# BLUESAT_WIRING_HARNESS_-_PROPOSED_V2.net
KiCad netlist of a schematic drawn in Altium Designer
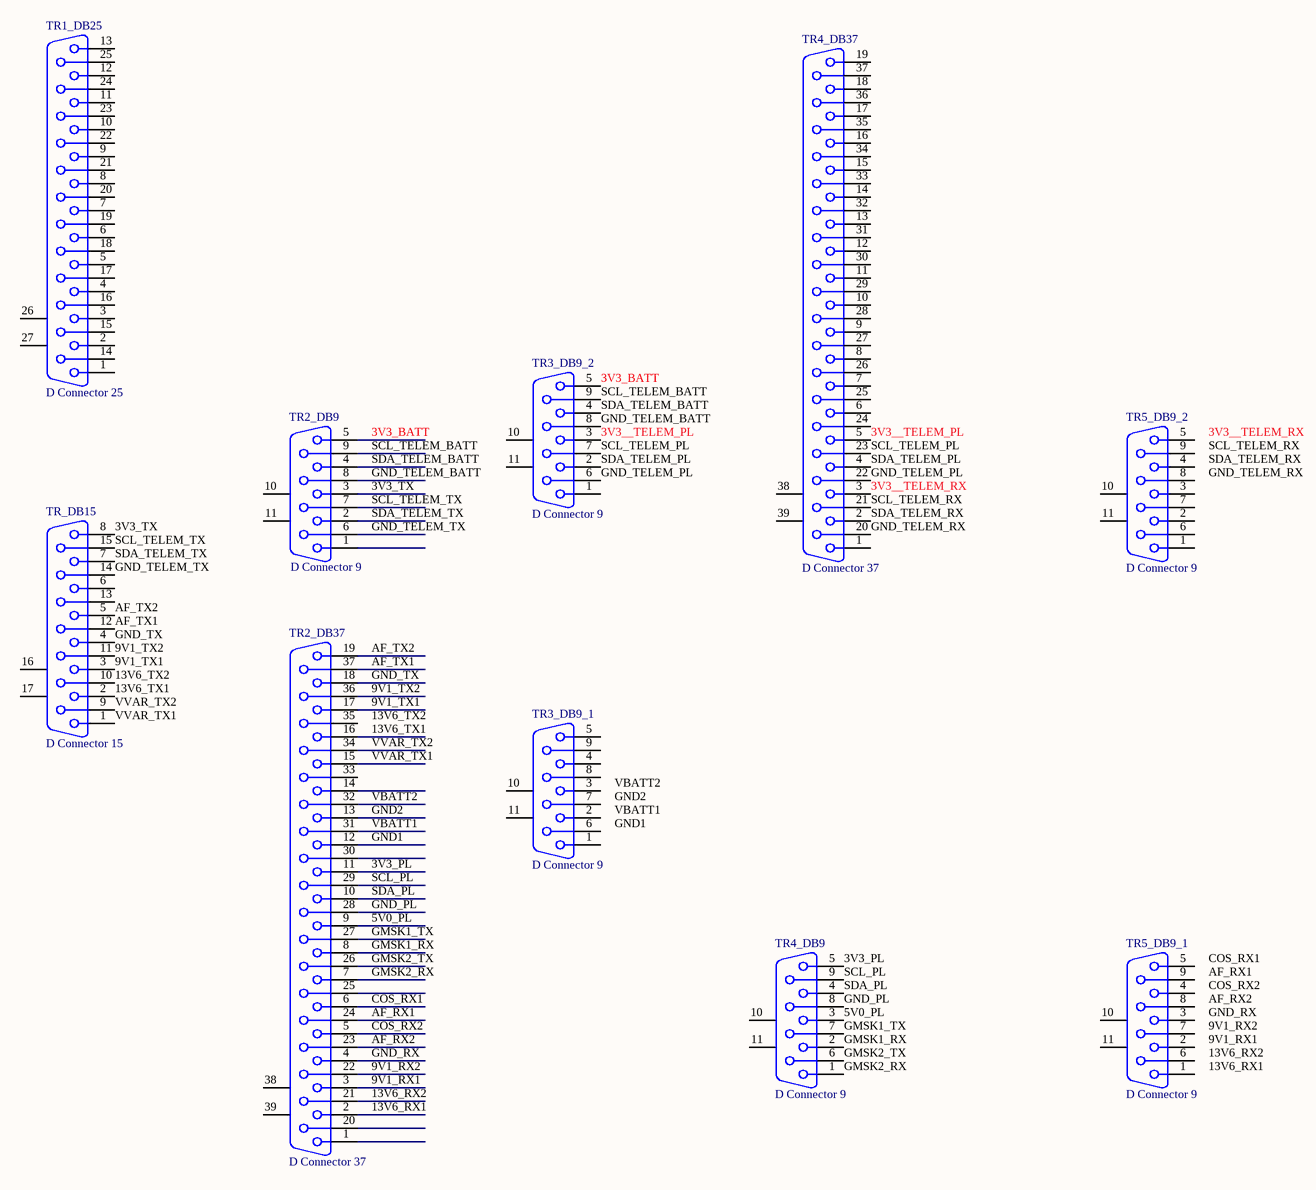
[diagram p0: BLUESAT WIRING HARNESS - PROPOSED V2.SchDoc]

(export (version "E")
  (design (tool "Eeschema 10.0.6"))
  (components
    (comp (ref "TR1_DB25")
      (value "D Connector 25")
      (footprint "DSUB1.385-2H25A")
      (description "Receptacle Assembly, 25 Position, Right Angle")
      (fields (field (name "PUBLISHER") "Altium Limited"))
      (libsource (lib "Miscellaneous Connectors") (part "D Connector 25"))
    )
    (comp (ref "TR2_DB9")
      (value "D Connector 9")
      (footprint "DSUB1.385-2H9")
      (description "Receptacle Assembly, 9 Position, Right Angle")
      (fields (field (name "PUBLISHER") "Altium Limited"))
      (libsource (lib "Miscellaneous Connectors") (part "D Connector 9"))
    )
    (comp (ref "TR2_DB37")
      (value "D Connector 37")
      (description "Receptacle Assembly, 37 Position, Right Angle")
      (fields (field (name "PUBLISHER") "Altium Limited"))
      (libsource (lib "Miscellaneous Connectors") (part "D Connector 37"))
    )
    (comp (ref "TR3_DB9_1")
      (value "D Connector 9")
      (footprint "DSUB1.385-2H9")
      (description "Receptacle Assembly, 9 Position, Right Angle")
      (fields (field (name "PUBLISHER") "Altium Limited"))
      (libsource (lib "Miscellaneous Connectors") (part "D Connector 9"))
    )
    (comp (ref "TR3_DB9_2")
      (value "D Connector 9")
      (footprint "DSUB1.385-2H9")
      (description "Receptacle Assembly, 9 Position, Right Angle")
      (fields (field (name "PUBLISHER") "Altium Limited"))
      (libsource (lib "Miscellaneous Connectors") (part "D Connector 9"))
    )
    (comp (ref "TR4_DB9")
      (value "D Connector 9")
      (footprint "DSUB1.385-2H9")
      (description "Receptacle Assembly, 9 Position, Right Angle")
      (fields (field (name "PUBLISHER") "Altium Limited"))
      (libsource (lib "Miscellaneous Connectors") (part "D Connector 9"))
    )
    (comp (ref "TR4_DB37")
      (value "D Connector 37")
      (description "Receptacle Assembly, 37 Position, Right Angle")
      (fields (field (name "PUBLISHER") "Altium Limited"))
      (libsource (lib "Miscellaneous Connectors") (part "D Connector 37"))
    )
    (comp (ref "TR5_DB9_1")
      (value "D Connector 9")
      (footprint "DSUB1.385-2H9")
      (description "Receptacle Assembly, 9 Position, Right Angle")
      (fields (field (name "PUBLISHER") "Altium Limited"))
      (libsource (lib "Miscellaneous Connectors") (part "D Connector 9"))
    )
    (comp (ref "TR5_DB9_2")
      (value "D Connector 9")
      (footprint "DSUB1.385-2H9")
      (description "Receptacle Assembly, 9 Position, Right Angle")
      (fields (field (name "PUBLISHER") "Altium Limited"))
      (libsource (lib "Miscellaneous Connectors") (part "D Connector 9"))
    )
    (comp (ref "TR_DB15")
      (value "D Connector 15")
      (footprint "DSUB1.385-2H15")
      (description "Receptacle Assembly, 15 Position, Right Angle")
      (fields (field (name "PUBLISHER") "Altium Limited"))
      (libsource (lib "Miscellaneous Connectors") (part "D Connector 15"))
    )
  )
  (nets
    (net (code "1") (name "/3V3_BATT") (class "Default")
      (node (ref "TR2_DB9") (pin "5") (pinfunction "5_5") (pintype "passive"))
      (node (ref "TR3_DB9_2") (pin "5") (pinfunction "5_5") (pintype "passive"))
    )
    (net (code "2") (name "/3V3_PL") (class "Default")
      (node (ref "TR2_DB37") (pin "11") (pinfunction "11_11") (pintype "passive"))
      (node (ref "TR4_DB9") (pin "5") (pinfunction "5_5") (pintype "passive"))
    )
    (net (code "3") (name "/3V3_TX") (class "Default")
      (node (ref "TR2_DB9") (pin "3") (pinfunction "3_3") (pintype "passive"))
      (node (ref "TR_DB15") (pin "8") (pinfunction "8_8") (pintype "passive"))
    )
    (net (code "4") (name "/3V3__TELEM_PL") (class "Default")
      (node (ref "TR3_DB9_2") (pin "3") (pinfunction "3_3") (pintype "passive"))
      (node (ref "TR4_DB37") (pin "5") (pinfunction "5_5") (pintype "passive"))
    )
    (net (code "5") (name "/3V3__TELEM_RX") (class "Default")
      (node (ref "TR4_DB37") (pin "3") (pinfunction "3_3") (pintype "passive"))
    )
    (net (code "6") (name "/5V0_PL") (class "Default")
      (node (ref "TR2_DB37") (pin "9") (pinfunction "9_9") (pintype "passive"))
      (node (ref "TR4_DB9") (pin "3") (pinfunction "3_3") (pintype "passive"))
    )
    (net (code "7") (name "/9V1_RX1") (class "Default")
      (node (ref "TR2_DB37") (pin "3") (pinfunction "3_3") (pintype "passive"))
    )
    (net (code "8") (name "/9V1_RX2") (class "Default")
      (node (ref "TR2_DB37") (pin "22") (pinfunction "22_22") (pintype "passive"))
    )
    (net (code "9") (name "/9V1_TX1") (class "Default")
      (node (ref "TR2_DB37") (pin "17") (pinfunction "17_17") (pintype "passive"))
      (node (ref "TR_DB15") (pin "3") (pinfunction "3_3") (pintype "passive"))
    )
    (net (code "10") (name "/9V1_TX2") (class "Default")
      (node (ref "TR2_DB37") (pin "36") (pinfunction "36_36") (pintype "passive"))
      (node (ref "TR_DB15") (pin "11") (pinfunction "11_11") (pintype "passive"))
    )
    (net (code "11") (name "/13V6_RX1") (class "Default")
      (node (ref "TR2_DB37") (pin "2") (pinfunction "2_2") (pintype "passive"))
    )
    (net (code "12") (name "/13V6_RX2") (class "Default")
      (node (ref "TR2_DB37") (pin "21") (pinfunction "21_21") (pintype "passive"))
    )
    (net (code "13") (name "/13V6_TX1") (class "Default")
      (node (ref "TR2_DB37") (pin "16") (pinfunction "16_16") (pintype "passive"))
      (node (ref "TR_DB15") (pin "2") (pinfunction "2_2") (pintype "passive"))
    )
    (net (code "14") (name "/13V6_TX2") (class "Default")
      (node (ref "TR_DB15") (pin "10") (pinfunction "10_10") (pintype "passive"))
    )
    (net (code "15") (name "/AF_RX1") (class "Default")
      (node (ref "TR2_DB37") (pin "24") (pinfunction "24_24") (pintype "passive"))
    )
    (net (code "16") (name "/AF_RX2") (class "Default")
      (node (ref "TR2_DB37") (pin "23") (pinfunction "23_23") (pintype "passive"))
    )
    (net (code "17") (name "/AF_TX1") (class "Default")
      (node (ref "TR2_DB37") (pin "37") (pinfunction "37_37") (pintype "passive"))
      (node (ref "TR_DB15") (pin "12") (pinfunction "12_12") (pintype "passive"))
    )
    (net (code "18") (name "/AF_TX2") (class "Default")
      (node (ref "TR2_DB37") (pin "19") (pinfunction "19_19") (pintype "passive"))
      (node (ref "TR_DB15") (pin "5") (pinfunction "5_5") (pintype "passive"))
    )
    (net (code "19") (name "/COS_RX1") (class "Default")
      (node (ref "TR2_DB37") (pin "6") (pinfunction "6_6") (pintype "passive"))
    )
    (net (code "20") (name "/COS_RX2") (class "Default")
      (node (ref "TR2_DB37") (pin "5") (pinfunction "5_5") (pintype "passive"))
    )
    (net (code "21") (name "/GMSK1_RX") (class "Default")
      (node (ref "TR2_DB37") (pin "8") (pinfunction "8_8") (pintype "passive"))
      (node (ref "TR4_DB9") (pin "2") (pinfunction "2_2") (pintype "passive"))
    )
    (net (code "22") (name "/GMSK1_TX") (class "Default")
      (node (ref "TR2_DB37") (pin "27") (pinfunction "27_27") (pintype "passive"))
      (node (ref "TR4_DB9") (pin "7") (pinfunction "7_7") (pintype "passive"))
    )
    (net (code "23") (name "/GMSK2_RX") (class "Default")
      (node (ref "TR2_DB37") (pin "7") (pinfunction "7_7") (pintype "passive"))
      (node (ref "TR4_DB9") (pin "1") (pinfunction "1_1") (pintype "passive"))
    )
    (net (code "24") (name "/GMSK2_TX") (class "Default")
      (node (ref "TR2_DB37") (pin "26") (pinfunction "26_26") (pintype "passive"))
      (node (ref "TR4_DB9") (pin "6") (pinfunction "6_6") (pintype "passive"))
    )
    (net (code "25") (name "/GND1") (class "Default")
      (node (ref "TR2_DB37") (pin "12") (pinfunction "12_12") (pintype "passive"))
    )
    (net (code "26") (name "/GND2") (class "Default")
      (node (ref "TR2_DB37") (pin "13") (pinfunction "13_13") (pintype "passive"))
    )
    (net (code "27") (name "/GND_PL") (class "Default")
      (node (ref "TR2_DB37") (pin "28") (pinfunction "28_28") (pintype "passive"))
      (node (ref "TR4_DB9") (pin "8") (pinfunction "8_8") (pintype "passive"))
    )
    (net (code "28") (name "/GND_RX") (class "Default")
      (node (ref "TR2_DB37") (pin "4") (pinfunction "4_4") (pintype "passive"))
    )
    (net (code "29") (name "/GND_TELEM_BATT") (class "Default")
      (node (ref "TR2_DB9") (pin "8") (pinfunction "8_8") (pintype "passive"))
      (node (ref "TR3_DB9_2") (pin "8") (pinfunction "8_8") (pintype "passive"))
    )
    (net (code "30") (name "/GND_TELEM_PL") (class "Default")
      (node (ref "TR3_DB9_2") (pin "6") (pinfunction "6_6") (pintype "passive"))
      (node (ref "TR4_DB37") (pin "22") (pinfunction "22_22") (pintype "passive"))
    )
    (net (code "31") (name "/GND_TELEM_RX") (class "Default")
      (node (ref "TR4_DB37") (pin "20") (pinfunction "20_20") (pintype "passive"))
    )
    (net (code "32") (name "/GND_TELEM_TX") (class "Default")
      (node (ref "TR2_DB9") (pin "6") (pinfunction "6_6") (pintype "passive"))
      (node (ref "TR_DB15") (pin "14") (pinfunction "14_14") (pintype "passive"))
    )
    (net (code "33") (name "/GND_TX") (class "Default")
      (node (ref "TR2_DB37") (pin "18") (pinfunction "18_18") (pintype "passive"))
      (node (ref "TR_DB15") (pin "4") (pinfunction "4_4") (pintype "passive"))
    )
    (net (code "34") (name "/SCL_PL") (class "Default")
      (node (ref "TR2_DB37") (pin "29") (pinfunction "29_29") (pintype "passive"))
      (node (ref "TR4_DB9") (pin "9") (pinfunction "9_9") (pintype "passive"))
    )
    (net (code "35") (name "/SCL_TELEM_BATT") (class "Default")
      (node (ref "TR2_DB9") (pin "9") (pinfunction "9_9") (pintype "passive"))
      (node (ref "TR3_DB9_2") (pin "9") (pinfunction "9_9") (pintype "passive"))
    )
    (net (code "36") (name "/SCL_TELEM_PL") (class "Default")
      (node (ref "TR3_DB9_2") (pin "7") (pinfunction "7_7") (pintype "passive"))
      (node (ref "TR4_DB37") (pin "23") (pinfunction "23_23") (pintype "passive"))
    )
    (net (code "37") (name "/SCL_TELEM_RX") (class "Default")
      (node (ref "TR4_DB37") (pin "21") (pinfunction "21_21") (pintype "passive"))
    )
    (net (code "38") (name "/SCL_TELEM_TX") (class "Default")
      (node (ref "TR2_DB9") (pin "7") (pinfunction "7_7") (pintype "passive"))
      (node (ref "TR_DB15") (pin "15") (pinfunction "15_15") (pintype "passive"))
    )
    (net (code "39") (name "/SDA_PL") (class "Default")
      (node (ref "TR2_DB37") (pin "10") (pinfunction "10_10") (pintype "passive"))
      (node (ref "TR4_DB9") (pin "4") (pinfunction "4_4") (pintype "passive"))
    )
    (net (code "40") (name "/SDA_TELEM_BATT") (class "Default")
      (node (ref "TR2_DB9") (pin "4") (pinfunction "4_4") (pintype "passive"))
      (node (ref "TR3_DB9_2") (pin "4") (pinfunction "4_4") (pintype "passive"))
    )
    (net (code "41") (name "/SDA_TELEM_PL") (class "Default")
      (node (ref "TR3_DB9_2") (pin "2") (pinfunction "2_2") (pintype "passive"))
      (node (ref "TR4_DB37") (pin "4") (pinfunction "4_4") (pintype "passive"))
    )
    (net (code "42") (name "/SDA_TELEM_RX") (class "Default")
      (node (ref "TR4_DB37") (pin "2") (pinfunction "2_2") (pintype "passive"))
    )
    (net (code "43") (name "/SDA_TELEM_TX") (class "Default")
      (node (ref "TR2_DB9") (pin "2") (pinfunction "2_2") (pintype "passive"))
      (node (ref "TR_DB15") (pin "7") (pinfunction "7_7") (pintype "passive"))
    )
    (net (code "44") (name "/VBATT1") (class "Default")
      (node (ref "TR2_DB37") (pin "31") (pinfunction "31_31") (pintype "passive"))
    )
    (net (code "45") (name "/VBATT2") (class "Default")
      (node (ref "TR2_DB37") (pin "32") (pinfunction "32_32") (pintype "passive"))
    )
    (net (code "46") (name "/VVAR_TX1") (class "Default")
      (node (ref "TR2_DB37") (pin "15") (pinfunction "15_15") (pintype "passive"))
      (node (ref "TR_DB15") (pin "1") (pinfunction "1_1") (pintype "passive"))
    )
    (net (code "47") (name "/VVAR_TX2") (class "Default")
      (node (ref "TR2_DB37") (pin "34") (pinfunction "34_34") (pintype "passive"))
      (node (ref "TR_DB15") (pin "9") (pinfunction "9_9") (pintype "passive"))
    )
    (net (code "48") (name "unconnected-(TR1_DB25-MH1-Pad26)") (class "Default")
      (node (ref "TR1_DB25") (pin "26") (pinfunction "MH1_26") (pintype "passive"))
    )
    (net (code "49") (name "unconnected-(TR1_DB25-MH2-Pad27)") (class "Default")
      (node (ref "TR1_DB25") (pin "27") (pinfunction "MH2_27") (pintype "passive"))
    )
    (net (code "50") (name "unconnected-(TR1_DB25-Pad1)") (class "Default")
      (node (ref "TR1_DB25") (pin "1") (pinfunction "1_1") (pintype "passive"))
    )
    (net (code "51") (name "unconnected-(TR1_DB25-Pad2)") (class "Default")
      (node (ref "TR1_DB25") (pin "2") (pinfunction "2_2") (pintype "passive"))
    )
    (net (code "52") (name "unconnected-(TR1_DB25-Pad3)") (class "Default")
      (node (ref "TR1_DB25") (pin "3") (pinfunction "3_3") (pintype "passive"))
    )
    (net (code "53") (name "unconnected-(TR1_DB25-Pad4)") (class "Default")
      (node (ref "TR1_DB25") (pin "4") (pinfunction "4_4") (pintype "passive"))
    )
    (net (code "54") (name "unconnected-(TR1_DB25-Pad5)") (class "Default")
      (node (ref "TR1_DB25") (pin "5") (pinfunction "5_5") (pintype "passive"))
    )
    (net (code "55") (name "unconnected-(TR1_DB25-Pad6)") (class "Default")
      (node (ref "TR1_DB25") (pin "6") (pinfunction "6_6") (pintype "passive"))
    )
    (net (code "56") (name "unconnected-(TR1_DB25-Pad7)") (class "Default")
      (node (ref "TR1_DB25") (pin "7") (pinfunction "7_7") (pintype "passive"))
    )
    (net (code "57") (name "unconnected-(TR1_DB25-Pad8)") (class "Default")
      (node (ref "TR1_DB25") (pin "8") (pinfunction "8_8") (pintype "passive"))
    )
    (net (code "58") (name "unconnected-(TR1_DB25-Pad9)") (class "Default")
      (node (ref "TR1_DB25") (pin "9") (pinfunction "9_9") (pintype "passive"))
    )
    (net (code "59") (name "unconnected-(TR1_DB25-Pad10)") (class "Default")
      (node (ref "TR1_DB25") (pin "10") (pinfunction "10_10") (pintype "passive"))
    )
    (net (code "60") (name "unconnected-(TR1_DB25-Pad11)") (class "Default")
      (node (ref "TR1_DB25") (pin "11") (pinfunction "11_11") (pintype "passive"))
    )
    (net (code "61") (name "unconnected-(TR1_DB25-Pad12)") (class "Default")
      (node (ref "TR1_DB25") (pin "12") (pinfunction "12_12") (pintype "passive"))
    )
    (net (code "62") (name "unconnected-(TR1_DB25-Pad13)") (class "Default")
      (node (ref "TR1_DB25") (pin "13") (pinfunction "13_13") (pintype "passive"))
    )
    (net (code "63") (name "unconnected-(TR1_DB25-Pad14)") (class "Default")
      (node (ref "TR1_DB25") (pin "14") (pinfunction "14_14") (pintype "passive"))
    )
    (net (code "64") (name "unconnected-(TR1_DB25-Pad15)") (class "Default")
      (node (ref "TR1_DB25") (pin "15") (pinfunction "15_15") (pintype "passive"))
    )
    (net (code "65") (name "unconnected-(TR1_DB25-Pad16)") (class "Default")
      (node (ref "TR1_DB25") (pin "16") (pinfunction "16_16") (pintype "passive"))
    )
    (net (code "66") (name "unconnected-(TR1_DB25-Pad17)") (class "Default")
      (node (ref "TR1_DB25") (pin "17") (pinfunction "17_17") (pintype "passive"))
    )
    (net (code "67") (name "unconnected-(TR1_DB25-Pad18)") (class "Default")
      (node (ref "TR1_DB25") (pin "18") (pinfunction "18_18") (pintype "passive"))
    )
    (net (code "68") (name "unconnected-(TR1_DB25-Pad19)") (class "Default")
      (node (ref "TR1_DB25") (pin "19") (pinfunction "19_19") (pintype "passive"))
    )
    (net (code "69") (name "unconnected-(TR1_DB25-Pad20)") (class "Default")
      (node (ref "TR1_DB25") (pin "20") (pinfunction "20_20") (pintype "passive"))
    )
    (net (code "70") (name "unconnected-(TR1_DB25-Pad21)") (class "Default")
      (node (ref "TR1_DB25") (pin "21") (pinfunction "21_21") (pintype "passive"))
    )
    (net (code "71") (name "unconnected-(TR1_DB25-Pad22)") (class "Default")
      (node (ref "TR1_DB25") (pin "22") (pinfunction "22_22") (pintype "passive"))
    )
    (net (code "72") (name "unconnected-(TR1_DB25-Pad23)") (class "Default")
      (node (ref "TR1_DB25") (pin "23") (pinfunction "23_23") (pintype "passive"))
    )
    (net (code "73") (name "unconnected-(TR1_DB25-Pad24)") (class "Default")
      (node (ref "TR1_DB25") (pin "24") (pinfunction "24_24") (pintype "passive"))
    )
    (net (code "74") (name "unconnected-(TR1_DB25-Pad25)") (class "Default")
      (node (ref "TR1_DB25") (pin "25") (pinfunction "25_25") (pintype "passive"))
    )
    (net (code "75") (name "unconnected-(TR2_DB9-MH1-Pad10)") (class "Default")
      (node (ref "TR2_DB9") (pin "10") (pinfunction "MH1_10") (pintype "passive"))
    )
    (net (code "76") (name "unconnected-(TR2_DB9-MH2-Pad11)") (class "Default")
      (node (ref "TR2_DB9") (pin "11") (pinfunction "MH2_11") (pintype "passive"))
    )
    (net (code "77") (name "unconnected-(TR2_DB9-Pad1)") (class "Default")
      (node (ref "TR2_DB9") (pin "1") (pinfunction "1_1") (pintype "passive"))
    )
    (net (code "78") (name "unconnected-(TR2_DB37-MH1-Pad38)") (class "Default")
      (node (ref "TR2_DB37") (pin "38") (pinfunction "MH1_38") (pintype "passive"))
    )
    (net (code "79") (name "unconnected-(TR2_DB37-MH2-Pad39)") (class "Default")
      (node (ref "TR2_DB37") (pin "39") (pinfunction "MH2_39") (pintype "passive"))
    )
    (net (code "80") (name "unconnected-(TR2_DB37-Pad1)") (class "Default")
      (node (ref "TR2_DB37") (pin "1") (pinfunction "1_1") (pintype "passive"))
    )
    (net (code "81") (name "unconnected-(TR2_DB37-Pad14)") (class "Default")
      (node (ref "TR2_DB37") (pin "14") (pinfunction "14_14") (pintype "passive"))
    )
    (net (code "82") (name "unconnected-(TR2_DB37-Pad20)") (class "Default")
      (node (ref "TR2_DB37") (pin "20") (pinfunction "20_20") (pintype "passive"))
    )
    (net (code "83") (name "unconnected-(TR2_DB37-Pad25)") (class "Default")
      (node (ref "TR2_DB37") (pin "25") (pinfunction "25_25") (pintype "passive"))
    )
    (net (code "84") (name "unconnected-(TR2_DB37-Pad30)") (class "Default")
      (node (ref "TR2_DB37") (pin "30") (pinfunction "30_30") (pintype "passive"))
    )
    (net (code "85") (name "unconnected-(TR2_DB37-Pad33)") (class "Default")
      (node (ref "TR2_DB37") (pin "33") (pinfunction "33_33") (pintype "passive"))
    )
    (net (code "86") (name "unconnected-(TR2_DB37-Pad35)") (class "Default")
      (node (ref "TR2_DB37") (pin "35") (pinfunction "35_35") (pintype "passive"))
    )
    (net (code "87") (name "unconnected-(TR3_DB9_1-MH1-Pad10)") (class "Default")
      (node (ref "TR3_DB9_1") (pin "10") (pinfunction "MH1_10") (pintype "passive"))
    )
    (net (code "88") (name "unconnected-(TR3_DB9_1-MH2-Pad11)") (class "Default")
      (node (ref "TR3_DB9_1") (pin "11") (pinfunction "MH2_11") (pintype "passive"))
    )
    (net (code "89") (name "unconnected-(TR3_DB9_1-Pad1)") (class "Default")
      (node (ref "TR3_DB9_1") (pin "1") (pinfunction "1_1") (pintype "passive"))
    )
    (net (code "90") (name "unconnected-(TR3_DB9_1-Pad2)") (class "Default")
      (node (ref "TR3_DB9_1") (pin "2") (pinfunction "2_2") (pintype "passive"))
    )
    (net (code "91") (name "unconnected-(TR3_DB9_1-Pad3)") (class "Default")
      (node (ref "TR3_DB9_1") (pin "3") (pinfunction "3_3") (pintype "passive"))
    )
    (net (code "92") (name "unconnected-(TR3_DB9_1-Pad4)") (class "Default")
      (node (ref "TR3_DB9_1") (pin "4") (pinfunction "4_4") (pintype "passive"))
    )
    (net (code "93") (name "unconnected-(TR3_DB9_1-Pad5)") (class "Default")
      (node (ref "TR3_DB9_1") (pin "5") (pinfunction "5_5") (pintype "passive"))
    )
    (net (code "94") (name "unconnected-(TR3_DB9_1-Pad6)") (class "Default")
      (node (ref "TR3_DB9_1") (pin "6") (pinfunction "6_6") (pintype "passive"))
    )
    (net (code "95") (name "unconnected-(TR3_DB9_1-Pad7)") (class "Default")
      (node (ref "TR3_DB9_1") (pin "7") (pinfunction "7_7") (pintype "passive"))
    )
    (net (code "96") (name "unconnected-(TR3_DB9_1-Pad8)") (class "Default")
      (node (ref "TR3_DB9_1") (pin "8") (pinfunction "8_8") (pintype "passive"))
    )
    (net (code "97") (name "unconnected-(TR3_DB9_1-Pad9)") (class "Default")
      (node (ref "TR3_DB9_1") (pin "9") (pinfunction "9_9") (pintype "passive"))
    )
    (net (code "98") (name "unconnected-(TR3_DB9_2-MH1-Pad10)") (class "Default")
      (node (ref "TR3_DB9_2") (pin "10") (pinfunction "MH1_10") (pintype "passive"))
    )
    (net (code "99") (name "unconnected-(TR3_DB9_2-MH2-Pad11)") (class "Default")
      (node (ref "TR3_DB9_2") (pin "11") (pinfunction "MH2_11") (pintype "passive"))
    )
    (net (code "100") (name "unconnected-(TR3_DB9_2-Pad1)") (class "Default")
      (node (ref "TR3_DB9_2") (pin "1") (pinfunction "1_1") (pintype "passive"))
    )
    (net (code "101") (name "unconnected-(TR4_DB9-MH1-Pad10)") (class "Default")
      (node (ref "TR4_DB9") (pin "10") (pinfunction "MH1_10") (pintype "passive"))
    )
    (net (code "102") (name "unconnected-(TR4_DB9-MH2-Pad11)") (class "Default")
      (node (ref "TR4_DB9") (pin "11") (pinfunction "MH2_11") (pintype "passive"))
    )
    (net (code "103") (name "unconnected-(TR4_DB37-MH1-Pad38)") (class "Default")
      (node (ref "TR4_DB37") (pin "38") (pinfunction "MH1_38") (pintype "passive"))
    )
    (net (code "104") (name "unconnected-(TR4_DB37-MH2-Pad39)") (class "Default")
      (node (ref "TR4_DB37") (pin "39") (pinfunction "MH2_39") (pintype "passive"))
    )
    (net (code "105") (name "unconnected-(TR4_DB37-Pad1)") (class "Default")
      (node (ref "TR4_DB37") (pin "1") (pinfunction "1_1") (pintype "passive"))
    )
    (net (code "106") (name "unconnected-(TR4_DB37-Pad6)") (class "Default")
      (node (ref "TR4_DB37") (pin "6") (pinfunction "6_6") (pintype "passive"))
    )
    (net (code "107") (name "unconnected-(TR4_DB37-Pad7)") (class "Default")
      (node (ref "TR4_DB37") (pin "7") (pinfunction "7_7") (pintype "passive"))
    )
    (net (code "108") (name "unconnected-(TR4_DB37-Pad8)") (class "Default")
      (node (ref "TR4_DB37") (pin "8") (pinfunction "8_8") (pintype "passive"))
    )
    (net (code "109") (name "unconnected-(TR4_DB37-Pad9)") (class "Default")
      (node (ref "TR4_DB37") (pin "9") (pinfunction "9_9") (pintype "passive"))
    )
    (net (code "110") (name "unconnected-(TR4_DB37-Pad10)") (class "Default")
      (node (ref "TR4_DB37") (pin "10") (pinfunction "10_10") (pintype "passive"))
    )
    (net (code "111") (name "unconnected-(TR4_DB37-Pad11)") (class "Default")
      (node (ref "TR4_DB37") (pin "11") (pinfunction "11_11") (pintype "passive"))
    )
    (net (code "112") (name "unconnected-(TR4_DB37-Pad12)") (class "Default")
      (node (ref "TR4_DB37") (pin "12") (pinfunction "12_12") (pintype "passive"))
    )
    (net (code "113") (name "unconnected-(TR4_DB37-Pad13)") (class "Default")
      (node (ref "TR4_DB37") (pin "13") (pinfunction "13_13") (pintype "passive"))
    )
    (net (code "114") (name "unconnected-(TR4_DB37-Pad14)") (class "Default")
      (node (ref "TR4_DB37") (pin "14") (pinfunction "14_14") (pintype "passive"))
    )
    (net (code "115") (name "unconnected-(TR4_DB37-Pad15)") (class "Default")
      (node (ref "TR4_DB37") (pin "15") (pinfunction "15_15") (pintype "passive"))
    )
    (net (code "116") (name "unconnected-(TR4_DB37-Pad16)") (class "Default")
      (node (ref "TR4_DB37") (pin "16") (pinfunction "16_16") (pintype "passive"))
    )
    (net (code "117") (name "unconnected-(TR4_DB37-Pad17)") (class "Default")
      (node (ref "TR4_DB37") (pin "17") (pinfunction "17_17") (pintype "passive"))
    )
    (net (code "118") (name "unconnected-(TR4_DB37-Pad18)") (class "Default")
      (node (ref "TR4_DB37") (pin "18") (pinfunction "18_18") (pintype "passive"))
    )
    (net (code "119") (name "unconnected-(TR4_DB37-Pad19)") (class "Default")
      (node (ref "TR4_DB37") (pin "19") (pinfunction "19_19") (pintype "passive"))
    )
    (net (code "120") (name "unconnected-(TR4_DB37-Pad24)") (class "Default")
      (node (ref "TR4_DB37") (pin "24") (pinfunction "24_24") (pintype "passive"))
    )
    (net (code "121") (name "unconnected-(TR4_DB37-Pad25)") (class "Default")
      (node (ref "TR4_DB37") (pin "25") (pinfunction "25_25") (pintype "passive"))
    )
    (net (code "122") (name "unconnected-(TR4_DB37-Pad26)") (class "Default")
      (node (ref "TR4_DB37") (pin "26") (pinfunction "26_26") (pintype "passive"))
    )
    (net (code "123") (name "unconnected-(TR4_DB37-Pad27)") (class "Default")
      (node (ref "TR4_DB37") (pin "27") (pinfunction "27_27") (pintype "passive"))
    )
    (net (code "124") (name "unconnected-(TR4_DB37-Pad28)") (class "Default")
      (node (ref "TR4_DB37") (pin "28") (pinfunction "28_28") (pintype "passive"))
    )
    (net (code "125") (name "unconnected-(TR4_DB37-Pad29)") (class "Default")
      (node (ref "TR4_DB37") (pin "29") (pinfunction "29_29") (pintype "passive"))
    )
    (net (code "126") (name "unconnected-(TR4_DB37-Pad30)") (class "Default")
      (node (ref "TR4_DB37") (pin "30") (pinfunction "30_30") (pintype "passive"))
    )
    (net (code "127") (name "unconnected-(TR4_DB37-Pad31)") (class "Default")
      (node (ref "TR4_DB37") (pin "31") (pinfunction "31_31") (pintype "passive"))
    )
    (net (code "128") (name "unconnected-(TR4_DB37-Pad32)") (class "Default")
      (node (ref "TR4_DB37") (pin "32") (pinfunction "32_32") (pintype "passive"))
    )
    (net (code "129") (name "unconnected-(TR4_DB37-Pad33)") (class "Default")
      (node (ref "TR4_DB37") (pin "33") (pinfunction "33_33") (pintype "passive"))
    )
    (net (code "130") (name "unconnected-(TR4_DB37-Pad34)") (class "Default")
      (node (ref "TR4_DB37") (pin "34") (pinfunction "34_34") (pintype "passive"))
    )
    (net (code "131") (name "unconnected-(TR4_DB37-Pad35)") (class "Default")
      (node (ref "TR4_DB37") (pin "35") (pinfunction "35_35") (pintype "passive"))
    )
    (net (code "132") (name "unconnected-(TR4_DB37-Pad36)") (class "Default")
      (node (ref "TR4_DB37") (pin "36") (pinfunction "36_36") (pintype "passive"))
    )
    (net (code "133") (name "unconnected-(TR4_DB37-Pad37)") (class "Default")
      (node (ref "TR4_DB37") (pin "37") (pinfunction "37_37") (pintype "passive"))
    )
    (net (code "134") (name "unconnected-(TR5_DB9_1-MH1-Pad10)") (class "Default")
      (node (ref "TR5_DB9_1") (pin "10") (pinfunction "MH1_10") (pintype "passive"))
    )
    (net (code "135") (name "unconnected-(TR5_DB9_1-MH2-Pad11)") (class "Default")
      (node (ref "TR5_DB9_1") (pin "11") (pinfunction "MH2_11") (pintype "passive"))
    )
    (net (code "136") (name "unconnected-(TR5_DB9_1-Pad1)") (class "Default")
      (node (ref "TR5_DB9_1") (pin "1") (pinfunction "1_1") (pintype "passive"))
    )
    (net (code "137") (name "unconnected-(TR5_DB9_1-Pad2)") (class "Default")
      (node (ref "TR5_DB9_1") (pin "2") (pinfunction "2_2") (pintype "passive"))
    )
    (net (code "138") (name "unconnected-(TR5_DB9_1-Pad3)") (class "Default")
      (node (ref "TR5_DB9_1") (pin "3") (pinfunction "3_3") (pintype "passive"))
    )
    (net (code "139") (name "unconnected-(TR5_DB9_1-Pad4)") (class "Default")
      (node (ref "TR5_DB9_1") (pin "4") (pinfunction "4_4") (pintype "passive"))
    )
    (net (code "140") (name "unconnected-(TR5_DB9_1-Pad5)") (class "Default")
      (node (ref "TR5_DB9_1") (pin "5") (pinfunction "5_5") (pintype "passive"))
    )
    (net (code "141") (name "unconnected-(TR5_DB9_1-Pad6)") (class "Default")
      (node (ref "TR5_DB9_1") (pin "6") (pinfunction "6_6") (pintype "passive"))
    )
    (net (code "142") (name "unconnected-(TR5_DB9_1-Pad7)") (class "Default")
      (node (ref "TR5_DB9_1") (pin "7") (pinfunction "7_7") (pintype "passive"))
    )
    (net (code "143") (name "unconnected-(TR5_DB9_1-Pad8)") (class "Default")
      (node (ref "TR5_DB9_1") (pin "8") (pinfunction "8_8") (pintype "passive"))
    )
    (net (code "144") (name "unconnected-(TR5_DB9_1-Pad9)") (class "Default")
      (node (ref "TR5_DB9_1") (pin "9") (pinfunction "9_9") (pintype "passive"))
    )
    (net (code "145") (name "unconnected-(TR5_DB9_2-MH1-Pad10)") (class "Default")
      (node (ref "TR5_DB9_2") (pin "10") (pinfunction "MH1_10") (pintype "passive"))
    )
    (net (code "146") (name "unconnected-(TR5_DB9_2-MH2-Pad11)") (class "Default")
      (node (ref "TR5_DB9_2") (pin "11") (pinfunction "MH2_11") (pintype "passive"))
    )
    (net (code "147") (name "unconnected-(TR5_DB9_2-Pad1)") (class "Default")
      (node (ref "TR5_DB9_2") (pin "1") (pinfunction "1_1") (pintype "passive"))
    )
    (net (code "148") (name "unconnected-(TR5_DB9_2-Pad2)") (class "Default")
      (node (ref "TR5_DB9_2") (pin "2") (pinfunction "2_2") (pintype "passive"))
    )
    (net (code "149") (name "unconnected-(TR5_DB9_2-Pad3)") (class "Default")
      (node (ref "TR5_DB9_2") (pin "3") (pinfunction "3_3") (pintype "passive"))
    )
    (net (code "150") (name "unconnected-(TR5_DB9_2-Pad4)") (class "Default")
      (node (ref "TR5_DB9_2") (pin "4") (pinfunction "4_4") (pintype "passive"))
    )
    (net (code "151") (name "unconnected-(TR5_DB9_2-Pad5)") (class "Default")
      (node (ref "TR5_DB9_2") (pin "5") (pinfunction "5_5") (pintype "passive"))
    )
    (net (code "152") (name "unconnected-(TR5_DB9_2-Pad6)") (class "Default")
      (node (ref "TR5_DB9_2") (pin "6") (pinfunction "6_6") (pintype "passive"))
    )
    (net (code "153") (name "unconnected-(TR5_DB9_2-Pad7)") (class "Default")
      (node (ref "TR5_DB9_2") (pin "7") (pinfunction "7_7") (pintype "passive"))
    )
    (net (code "154") (name "unconnected-(TR5_DB9_2-Pad8)") (class "Default")
      (node (ref "TR5_DB9_2") (pin "8") (pinfunction "8_8") (pintype "passive"))
    )
    (net (code "155") (name "unconnected-(TR5_DB9_2-Pad9)") (class "Default")
      (node (ref "TR5_DB9_2") (pin "9") (pinfunction "9_9") (pintype "passive"))
    )
    (net (code "156") (name "unconnected-(TR_DB15-MH1-Pad16)") (class "Default")
      (node (ref "TR_DB15") (pin "16") (pinfunction "MH1_16") (pintype "passive"))
    )
    (net (code "157") (name "unconnected-(TR_DB15-MH2-Pad17)") (class "Default")
      (node (ref "TR_DB15") (pin "17") (pinfunction "MH2_17") (pintype "passive"))
    )
    (net (code "158") (name "unconnected-(TR_DB15-Pad6)") (class "Default")
      (node (ref "TR_DB15") (pin "6") (pinfunction "6_6") (pintype "passive"))
    )
    (net (code "159") (name "unconnected-(TR_DB15-Pad13)") (class "Default")
      (node (ref "TR_DB15") (pin "13") (pinfunction "13_13") (pintype "passive"))
    )
  )
)
